# rat.net
KiCad netlist of a schematic drawn in EAGLE
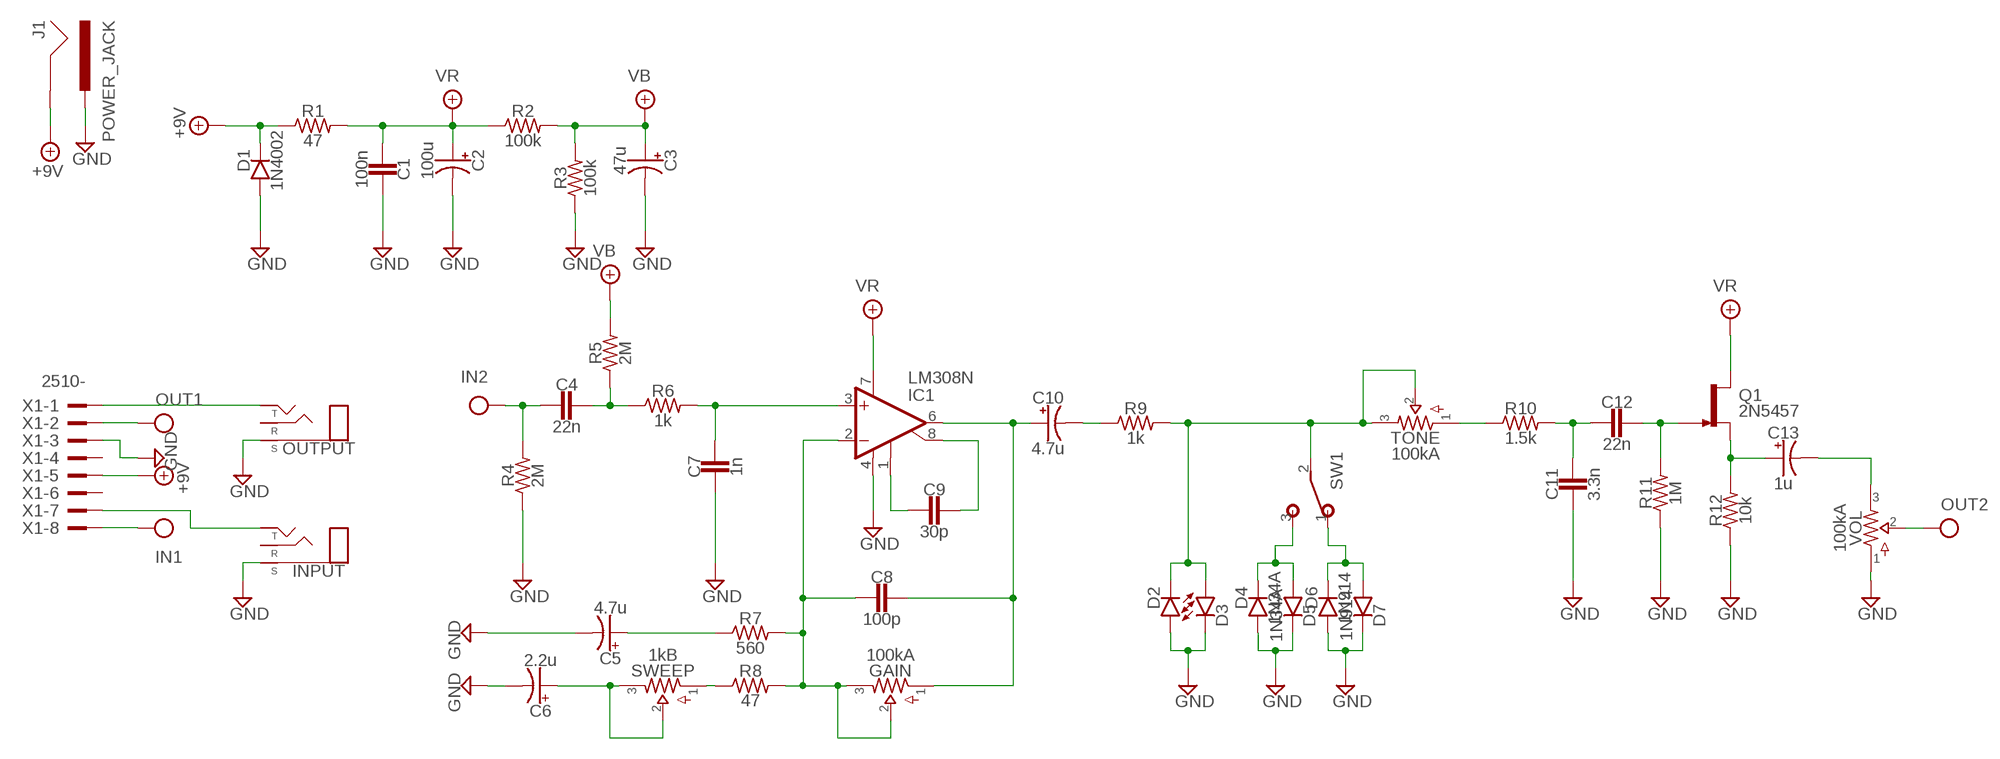
[diagram p0: schematic, sheet 1]

(export (version "E")
  (design (tool "Eeschema 10.0.6"))
  (components
    (comp (ref "C1")
      (value "100n")
      (footprint "eagle-import:050X030_025_2")
      (libsource (lib "eagle-import") (part "CER/FILM2"))
    )
    (comp (ref "C2")
      (value "100u")
      (footprint "eagle-import:040_020")
      (libsource (lib "eagle-import") (part "0400"))
    )
    (comp (ref "C3")
      (value "47u")
      (footprint "eagle-import:040_020")
      (libsource (lib "eagle-import") (part "0400"))
    )
    (comp (ref "C4")
      (value "22n")
      (footprint "eagle-import:BOX_SMALL")
      (libsource (lib "eagle-import") (part "CER/FILMBOX.1"))
    )
    (comp (ref "C5")
      (value "4.7u")
      (footprint "eagle-import:050_020")
      (libsource (lib "eagle-import") (part "0500"))
    )
    (comp (ref "C6")
      (value "2.2u")
      (footprint "eagle-import:050_020")
      (libsource (lib "eagle-import") (part "0500"))
    )
    (comp (ref "C7")
      (value "1n")
      (footprint "eagle-import:BOX_SMALL")
      (libsource (lib "eagle-import") (part "CER/FILMBOX.1"))
    )
    (comp (ref "C8")
      (value "100p")
      (footprint "eagle-import:050X030_025_2")
      (libsource (lib "eagle-import") (part "CER/FILM2"))
    )
    (comp (ref "C9")
      (value "30p")
      (footprint "eagle-import:050X030_025_2")
      (libsource (lib "eagle-import") (part "CER/FILM2"))
    )
    (comp (ref "C10")
      (value "4.7u")
      (footprint "eagle-import:050_020")
      (libsource (lib "eagle-import") (part "0500"))
    )
    (comp (ref "C11")
      (value "3.3n")
      (footprint "eagle-import:BOX_SMALL")
      (libsource (lib "eagle-import") (part "CER/FILMBOX.1"))
    )
    (comp (ref "C12")
      (value "22n")
      (footprint "eagle-import:BOX_SMALL")
      (libsource (lib "eagle-import") (part "CER/FILMBOX.1"))
    )
    (comp (ref "C13")
      (value "1u")
      (footprint "eagle-import:050_020")
      (libsource (lib "eagle-import") (part "0500"))
    )
    (comp (ref "D1")
      (value "1N4002")
      (footprint "eagle-import:DO41-2")
      (libsource (lib "eagle-import") (part "DO41.2"))
    )
    (comp (ref "D2")
      (value "LED")
      (footprint "eagle-import:3MM_D")
      (libsource (lib "eagle-import") (part "LED"))
    )
    (comp (ref "D3")
      (value "LED")
      (footprint "eagle-import:3MM_D")
      (libsource (lib "eagle-import") (part "LED"))
    )
    (comp (ref "D4")
      (value "1N34A")
      (footprint "eagle-import:DO35-2")
      (libsource (lib "eagle-import") (part "DO35.2"))
    )
    (comp (ref "D5")
      (value "1N34A")
      (footprint "eagle-import:DO35-2")
      (libsource (lib "eagle-import") (part "DO35.2"))
    )
    (comp (ref "D6")
      (value "1N914")
      (footprint "eagle-import:DO35-2")
      (libsource (lib "eagle-import") (part "DO35.2"))
    )
    (comp (ref "D7")
      (value "1N914")
      (footprint "eagle-import:DO35-2")
      (libsource (lib "eagle-import") (part "DO35.2"))
    )
    (comp (ref "GAIN")
      (value "100kA")
      (footprint "eagle-import:16MM")
      (libsource (lib "eagle-import") (part "POTS16MM"))
    )
    (comp (ref "IC1")
      (value "LM308N")
      (footprint "eagle-import:DIL08")
      (libsource (lib "eagle-import") (part "LM308N"))
    )
    (comp (ref "INPUT")
      (value "STEREONMJ")
      (footprint "eagle-import:NMJ6HCD2")
      (libsource (lib "eagle-import") (part "STEREONMJ"))
    )
    (comp (ref "J1")
      (value "POWER_JACK")
      (footprint "eagle-import:POWER_JACK_PTH")
      (libsource (lib "eagle-import") (part "POWER_JACK"))
    )
    (comp (ref "OUTPUT")
      (value "STEREONMJ")
      (footprint "eagle-import:NMJ6HCD2")
      (libsource (lib "eagle-import") (part "STEREONMJ"))
    )
    (comp (ref "Q1")
      (value "2N5457")
      (footprint "eagle-import:TO92-")
      (libsource (lib "eagle-import") (part "2N5457"))
    )
    (comp (ref "R1")
      (value "47")
      (footprint "eagle-import:R0207_3")
      (libsource (lib "eagle-import") (part "R_.3B"))
    )
    (comp (ref "R2")
      (value "100k")
      (footprint "eagle-import:R0207_3")
      (libsource (lib "eagle-import") (part "R_.3B"))
    )
    (comp (ref "R3")
      (value "100k")
      (footprint "eagle-import:R0207_3")
      (libsource (lib "eagle-import") (part "R_.3B"))
    )
    (comp (ref "R4")
      (value "2M")
      (footprint "eagle-import:R0207_3")
      (libsource (lib "eagle-import") (part "R_.3B"))
    )
    (comp (ref "R5")
      (value "2M")
      (footprint "eagle-import:R0207_3")
      (libsource (lib "eagle-import") (part "R_.3B"))
    )
    (comp (ref "R6")
      (value "1k")
      (footprint "eagle-import:R0207_3")
      (libsource (lib "eagle-import") (part "R_.3B"))
    )
    (comp (ref "R7")
      (value "560")
      (footprint "eagle-import:R0207_3")
      (libsource (lib "eagle-import") (part "R_.3B"))
    )
    (comp (ref "R8")
      (value "47")
      (footprint "eagle-import:R0207_3")
      (libsource (lib "eagle-import") (part "R_.3B"))
    )
    (comp (ref "R9")
      (value "1k")
      (footprint "eagle-import:R0207_3")
      (libsource (lib "eagle-import") (part "R_.3B"))
    )
    (comp (ref "R10")
      (value "1.5k")
      (footprint "eagle-import:R0207_3")
      (libsource (lib "eagle-import") (part "R_.3B"))
    )
    (comp (ref "R11")
      (value "1M")
      (footprint "eagle-import:R0207_3")
      (libsource (lib "eagle-import") (part "R_.3B"))
    )
    (comp (ref "R12")
      (value "10k")
      (footprint "eagle-import:R0207_3")
      (libsource (lib "eagle-import") (part "R_.3B"))
    )
    (comp (ref "SW1")
      (value "SPDT")
      (footprint "eagle-import:M9040P")
      (libsource (lib "eagle-import") (part "SPDT"))
    )
    (comp (ref "SWEEP")
      (value "1kB")
      (footprint "eagle-import:16MM")
      (libsource (lib "eagle-import") (part "POTS16MM"))
    )
    (comp (ref "TONE")
      (value "100kA")
      (footprint "eagle-import:16MM")
      (libsource (lib "eagle-import") (part "POTS16MM"))
    )
    (comp (ref "VOL")
      (value "100kA")
      (footprint "eagle-import:16MM")
      (libsource (lib "eagle-import") (part "POTS16MM"))
    )
    (comp (ref "X1")
      (value "2510-")
      (footprint "eagle-import:PAK100_2500-10")
      (fields (field (name "MF") "3M") (field (name "MPN") "2510-6002UB"))
      (libsource (lib "eagle-import") (part "2510-"))
    )
  )
  (nets
    (net (code "1") (name "+9V") (class "Default")
      (node (ref "D1") (pin "C") (pinfunction "C_C") (pintype "passive"))
      (node (ref "J1") (pin "GND") (pinfunction "GND_GND") (pintype "bidirectional"))
      (node (ref "R1") (pin "1") (pinfunction "1_1") (pintype "passive"))
      (node (ref "X1") (pin "5") (pinfunction "KL_5") (pintype "passive"))
    )
    (net (code "2") (name "GND") (class "Default")
      (node (ref "C1") (pin "1") (pinfunction "1_1") (pintype "passive"))
      (node (ref "C11") (pin "2") (pinfunction "2_2") (pintype "passive"))
      (node (ref "C2") (pin "-") (pinfunction "-_-") (pintype "passive"))
      (node (ref "C3") (pin "-") (pinfunction "-_-") (pintype "passive"))
      (node (ref "C5") (pin "-") (pinfunction "-_-") (pintype "passive"))
      (node (ref "C6") (pin "-") (pinfunction "-_-") (pintype "passive"))
      (node (ref "C7") (pin "2") (pinfunction "2_2") (pintype "passive"))
      (node (ref "D1") (pin "A") (pinfunction "A_A") (pintype "passive"))
      (node (ref "D2") (pin "ANODE") (pinfunction "A_ANODE") (pintype "passive"))
      (node (ref "D3") (pin "P$1") (pinfunction "C_P$1") (pintype "passive"))
      (node (ref "D4") (pin "A") (pinfunction "A_A") (pintype "passive"))
      (node (ref "D5") (pin "C") (pinfunction "C_C") (pintype "passive"))
      (node (ref "D6") (pin "A") (pinfunction "A_A") (pintype "passive"))
      (node (ref "D7") (pin "C") (pinfunction "C_C") (pintype "passive"))
      (node (ref "IC1") (pin "4") (pinfunction "V-_4") (pintype "power_in"))
      (node (ref "INPUT") (pin "S") (pinfunction "S_S") (pintype "passive"))
      (node (ref "J1") (pin "PWR") (pinfunction "PWR_PWR") (pintype "bidirectional"))
      (node (ref "OUTPUT") (pin "S") (pinfunction "S_S") (pintype "passive"))
      (node (ref "R11") (pin "1") (pinfunction "1_1") (pintype "passive"))
      (node (ref "R12") (pin "1") (pinfunction "1_1") (pintype "passive"))
      (node (ref "R3") (pin "1") (pinfunction "1_1") (pintype "passive"))
      (node (ref "R4") (pin "1") (pinfunction "1_1") (pintype "passive"))
      (node (ref "VOL") (pin "1") (pinfunction "1_1") (pintype "passive"))
      (node (ref "X1") (pin "3") (pinfunction "KL_3") (pintype "passive"))
    )
    (net (code "3") (name "IN") (class "Default")
      (node (ref "C4") (pin "2") (pinfunction "2_2") (pintype "passive"))
      (node (ref "R4") (pin "2") (pinfunction "2_2") (pintype "passive"))
      (node (ref "X1") (pin "8") (pinfunction "KL_8") (pintype "passive"))
    )
    (net (code "4") (name "Net-(C4-Pad1)") (class "Default")
      (node (ref "C4") (pin "1") (pinfunction "1_1") (pintype "passive"))
      (node (ref "R5") (pin "1") (pinfunction "1_1") (pintype "passive"))
      (node (ref "R6") (pin "1") (pinfunction "1_1") (pintype "passive"))
    )
    (net (code "5") (name "Net-(C5-Pad+)") (class "Default")
      (node (ref "C5") (pin "+") (pinfunction "+_+") (pintype "passive"))
      (node (ref "R7") (pin "1") (pinfunction "1_1") (pintype "passive"))
    )
    (net (code "6") (name "Net-(C6-Pad+)") (class "Default")
      (node (ref "C6") (pin "+") (pinfunction "+_+") (pintype "passive"))
      (node (ref "SWEEP") (pin "2") (pinfunction "2_2") (pintype "passive"))
      (node (ref "SWEEP") (pin "3") (pinfunction "3_3") (pintype "passive"))
    )
    (net (code "7") (name "Net-(C10-Pad-)") (class "Default")
      (node (ref "C10") (pin "-") (pinfunction "-_-") (pintype "passive"))
      (node (ref "R9") (pin "1") (pinfunction "1_1") (pintype "passive"))
    )
    (net (code "8") (name "Net-(C11-Pad1)") (class "Default")
      (node (ref "C11") (pin "1") (pinfunction "1_1") (pintype "passive"))
      (node (ref "C12") (pin "2") (pinfunction "2_2") (pintype "passive"))
      (node (ref "R10") (pin "2") (pinfunction "2_2") (pintype "passive"))
    )
    (net (code "9") (name "Net-(C13-Pad-)") (class "Default")
      (node (ref "C13") (pin "-") (pinfunction "-_-") (pintype "passive"))
      (node (ref "VOL") (pin "3") (pinfunction "3_3") (pintype "passive"))
    )
    (net (code "10") (name "Net-(D2-C)") (class "Default")
      (node (ref "D2") (pin "P$1") (pinfunction "C_P$1") (pintype "passive"))
      (node (ref "D3") (pin "ANODE") (pinfunction "A_ANODE") (pintype "passive"))
      (node (ref "R9") (pin "2") (pinfunction "2_2") (pintype "passive"))
      (node (ref "SW1") (pin "2") (pinfunction "P_2") (pintype "passive"))
      (node (ref "TONE") (pin "2") (pinfunction "2_2") (pintype "passive"))
      (node (ref "TONE") (pin "3") (pinfunction "3_3") (pintype "passive"))
    )
    (net (code "11") (name "Net-(IC1-+IN)") (class "Default")
      (node (ref "C7") (pin "1") (pinfunction "1_1") (pintype "passive"))
      (node (ref "IC1") (pin "3") (pinfunction "+IN_3") (pintype "input"))
      (node (ref "R6") (pin "2") (pinfunction "2_2") (pintype "passive"))
    )
    (net (code "12") (name "Net-(IC1--IN)") (class "Default")
      (node (ref "C8") (pin "2") (pinfunction "2_2") (pintype "passive"))
      (node (ref "GAIN") (pin "2") (pinfunction "2_2") (pintype "passive"))
      (node (ref "GAIN") (pin "3") (pinfunction "3_3") (pintype "passive"))
      (node (ref "IC1") (pin "2") (pinfunction "-IN_2") (pintype "input"))
      (node (ref "R7") (pin "2") (pinfunction "2_2") (pintype "passive"))
      (node (ref "R8") (pin "2") (pinfunction "2_2") (pintype "passive"))
    )
    (net (code "13") (name "Net-(IC1-CMP1)") (class "Default")
      (node (ref "C9") (pin "2") (pinfunction "2_2") (pintype "passive"))
      (node (ref "IC1") (pin "1") (pinfunction "CMP1_1") (pintype "passive"))
    )
    (net (code "14") (name "Net-(IC1-CMP2)") (class "Default")
      (node (ref "C9") (pin "1") (pinfunction "1_1") (pintype "passive"))
      (node (ref "IC1") (pin "8") (pinfunction "CMP2_8") (pintype "passive"))
    )
    (net (code "15") (name "Net-(IC1-OUT)") (class "Default")
      (node (ref "C10") (pin "+") (pinfunction "+_+") (pintype "passive"))
      (node (ref "C8") (pin "1") (pinfunction "1_1") (pintype "passive"))
      (node (ref "GAIN") (pin "1") (pinfunction "1_1") (pintype "passive"))
      (node (ref "IC1") (pin "6") (pinfunction "OUT_6") (pintype "output"))
    )
    (net (code "16") (name "Net-(Q1-G)") (class "Default")
      (node (ref "C12") (pin "1") (pinfunction "1_1") (pintype "passive"))
      (node (ref "Q1") (pin "1") (pinfunction "G_1") (pintype "passive"))
      (node (ref "R11") (pin "2") (pinfunction "2_2") (pintype "passive"))
    )
    (net (code "17") (name "Net-(Q1-S)") (class "Default")
      (node (ref "C13") (pin "+") (pinfunction "+_+") (pintype "passive"))
      (node (ref "Q1") (pin "2") (pinfunction "S_2") (pintype "passive"))
      (node (ref "R12") (pin "2") (pinfunction "2_2") (pintype "passive"))
    )
    (net (code "18") (name "Net-(R8-Pad1)") (class "Default")
      (node (ref "R8") (pin "1") (pinfunction "1_1") (pintype "passive"))
      (node (ref "SWEEP") (pin "1") (pinfunction "1_1") (pintype "passive"))
    )
    (net (code "19") (name "Net-(R10-Pad1)") (class "Default")
      (node (ref "R10") (pin "1") (pinfunction "1_1") (pintype "passive"))
      (node (ref "TONE") (pin "1") (pinfunction "1_1") (pintype "passive"))
    )
    (net (code "20") (name "Net-(SW1-O)") (class "Default")
      (node (ref "D6") (pin "C") (pinfunction "C_C") (pintype "passive"))
      (node (ref "D7") (pin "A") (pinfunction "A_A") (pintype "passive"))
      (node (ref "SW1") (pin "1") (pinfunction "O_1") (pintype "passive"))
    )
    (net (code "21") (name "Net-(SW1-S)") (class "Default")
      (node (ref "D4") (pin "C") (pinfunction "C_C") (pintype "passive"))
      (node (ref "D5") (pin "A") (pinfunction "A_A") (pintype "passive"))
      (node (ref "SW1") (pin "3") (pinfunction "S_3") (pintype "passive"))
    )
    (net (code "22") (name "Net-(X1A-KL)") (class "Default")
      (node (ref "OUTPUT") (pin "T") (pinfunction "T_T") (pintype "passive"))
      (node (ref "X1") (pin "1") (pinfunction "KL_1") (pintype "passive"))
    )
    (net (code "23") (name "Net-(X1G-KL)") (class "Default")
      (node (ref "INPUT") (pin "T") (pinfunction "T_T") (pintype "passive"))
      (node (ref "X1") (pin "7") (pinfunction "KL_7") (pintype "passive"))
    )
    (net (code "24") (name "OUT") (class "Default")
      (node (ref "VOL") (pin "2") (pinfunction "2_2") (pintype "passive"))
      (node (ref "X1") (pin "2") (pinfunction "KL_2") (pintype "passive"))
    )
    (net (code "25") (name "VB") (class "Default")
      (node (ref "C3") (pin "+") (pinfunction "+_+") (pintype "passive"))
      (node (ref "R2") (pin "2") (pinfunction "2_2") (pintype "passive"))
      (node (ref "R3") (pin "2") (pinfunction "2_2") (pintype "passive"))
      (node (ref "R5") (pin "2") (pinfunction "2_2") (pintype "passive"))
    )
    (net (code "26") (name "VR") (class "Default")
      (node (ref "C1") (pin "2") (pinfunction "2_2") (pintype "passive"))
      (node (ref "C2") (pin "+") (pinfunction "+_+") (pintype "passive"))
      (node (ref "IC1") (pin "7") (pinfunction "V+_7") (pintype "power_in"))
      (node (ref "Q1") (pin "3") (pinfunction "D_3") (pintype "passive"))
      (node (ref "R1") (pin "2") (pinfunction "2_2") (pintype "passive"))
      (node (ref "R2") (pin "1") (pinfunction "1_1") (pintype "passive"))
    )
    (net (code "27") (name "unconnected-(INPUT-PadR)") (class "Default")
      (node (ref "INPUT") (pin "R") (pinfunction "R_R") (pintype "passive"))
    )
    (net (code "28") (name "unconnected-(OUTPUT-PadR)") (class "Default")
      (node (ref "OUTPUT") (pin "R") (pinfunction "R_R") (pintype "passive"))
    )
    (net (code "29") (name "unconnected-(X1D-KL-Pad4)") (class "Default")
      (node (ref "X1") (pin "4") (pinfunction "KL_4") (pintype "passive"))
    )
    (net (code "30") (name "unconnected-(X1F-KL-Pad6)") (class "Default")
      (node (ref "X1") (pin "6") (pinfunction "KL_6") (pintype "passive"))
    )
  )
)
